# plugV15.net
KiCad netlist of a schematic drawn in EAGLE
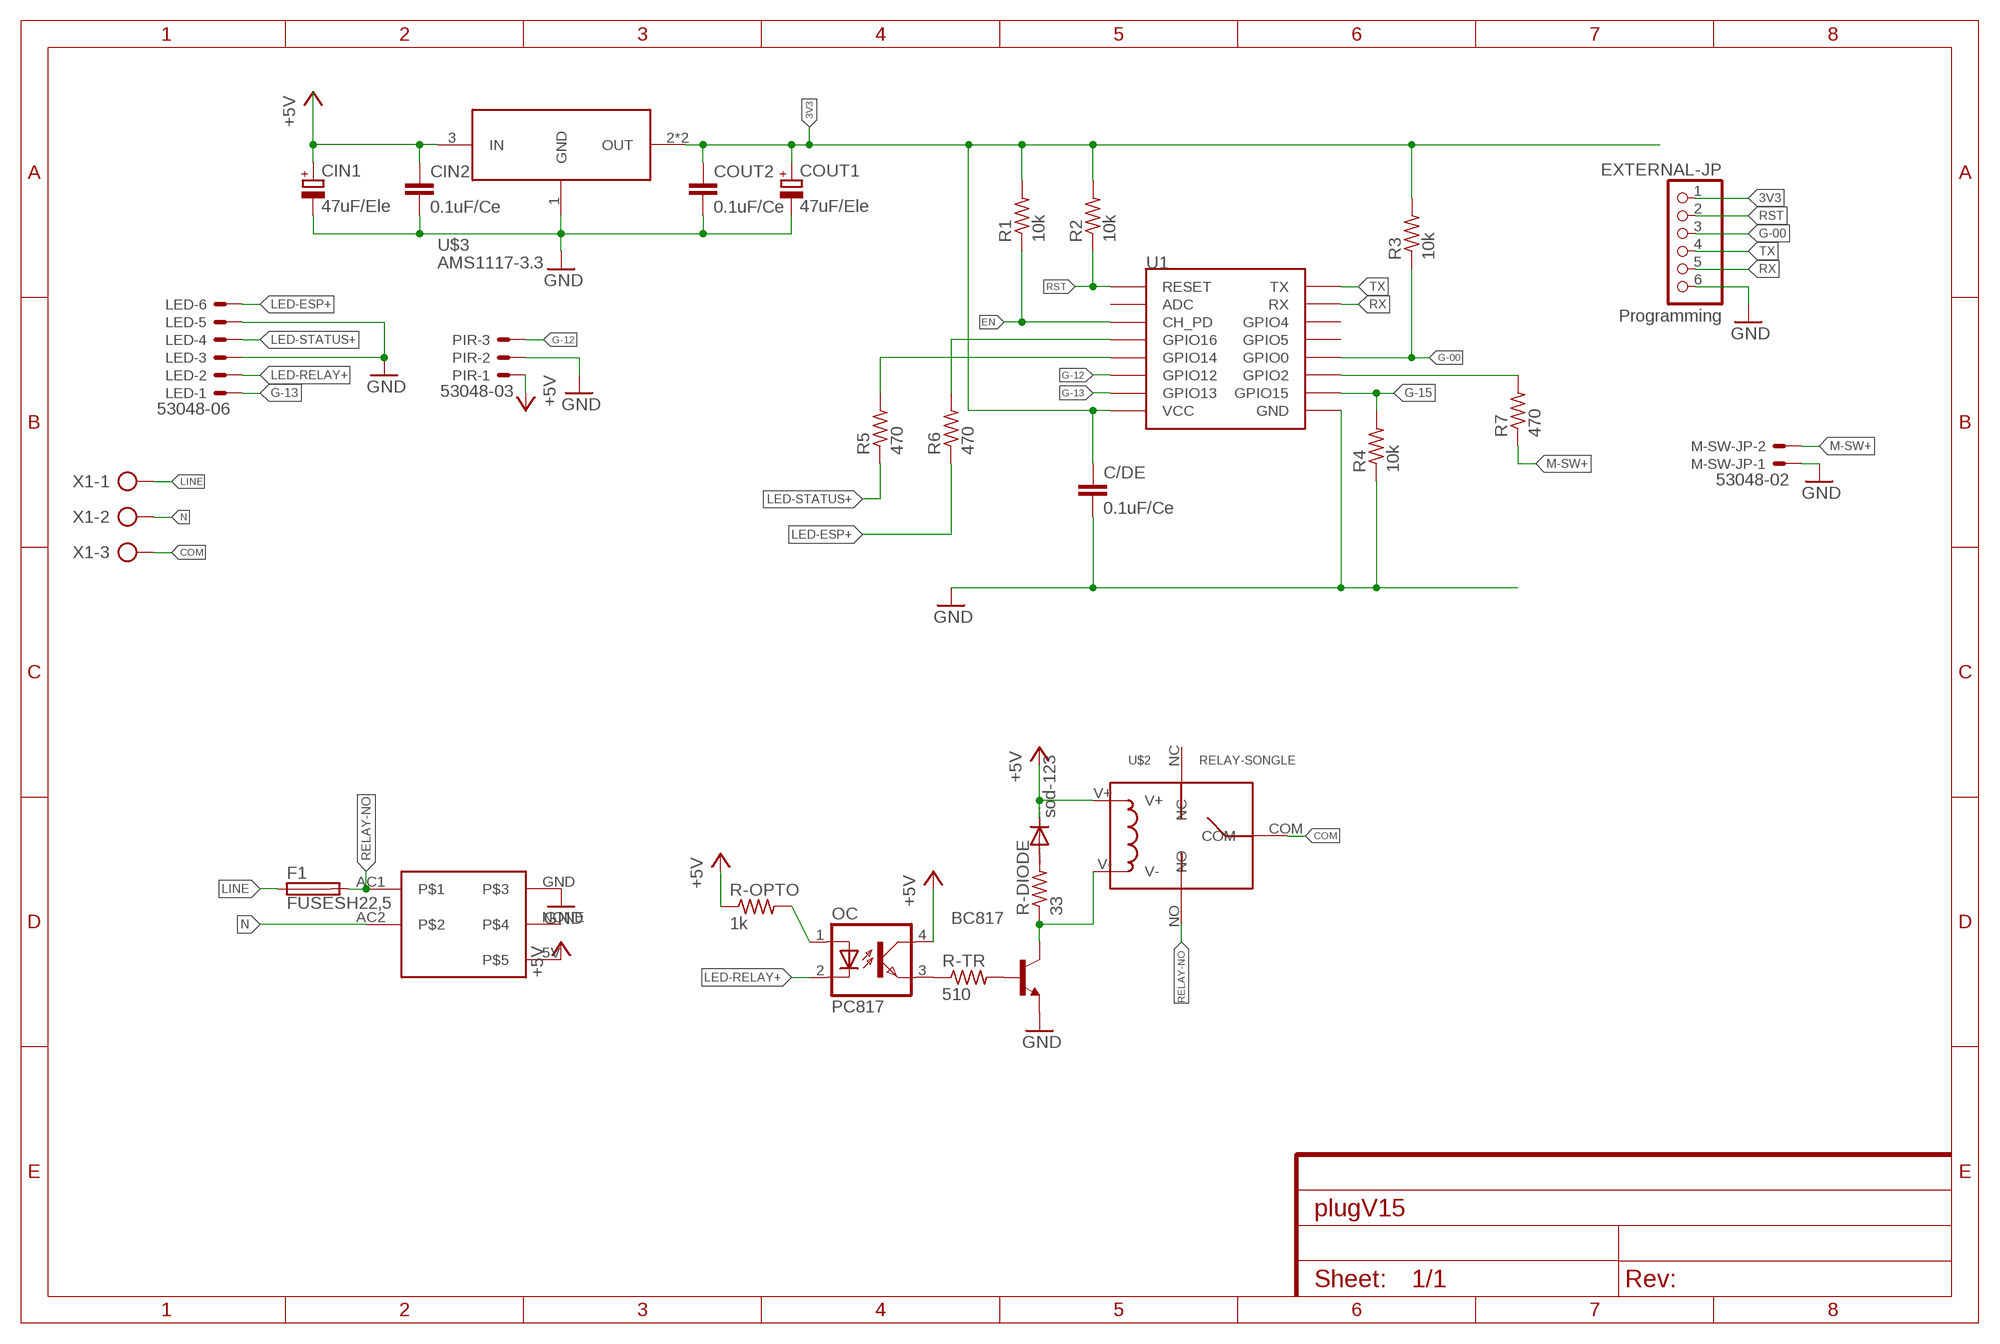
[diagram p0: schematic, sheet 1]

(export (version "E")
  (design (tool "Eeschema 10.0.6"))
  (components
    (comp (ref "1N4148")
      (value "sod-123")
      (footprint "eagle-import:SOD-123_MINI-SMA")
      (libsource (lib "eagle-import") (part "CGRM400-G1"))
    )
    (comp (ref "BC817")
      (value "BC817-NPN-SOT23-BEC")
      (footprint "eagle-import:SOT23-BEC")
      (libsource (lib "eagle-import") (part "-NPN-SOT23-BECBC817"))
    )
    (comp (ref "C/DE")
      (value "0.1uF/Ce")
      (footprint "eagle-import:C0805")
      (libsource (lib "eagle-import") (part "C-EUC0805"))
    )
    (comp (ref "CIN1")
      (value "47uF/Ele")
      (footprint "eagle-import:E2-5")
      (libsource (lib "eagle-import") (part "CPOL-EUE2-5"))
    )
    (comp (ref "CIN2")
      (value "0.1uF/Ce")
      (footprint "eagle-import:C0805")
      (libsource (lib "eagle-import") (part "C-EUC0805"))
    )
    (comp (ref "COUT1")
      (value "47uF/Ele")
      (footprint "eagle-import:E2-5")
      (libsource (lib "eagle-import") (part "CPOL-EUE2-5"))
    )
    (comp (ref "COUT2")
      (value "0.1uF/Ce")
      (footprint "eagle-import:C0805")
      (libsource (lib "eagle-import") (part "C-EUC0805"))
    )
    (comp (ref "EXTERNAL-JP")
      (value "Programming")
      (footprint "eagle-import:1X06")
      (libsource (lib "eagle-import") (part "PINHD-1X6"))
    )
    (comp (ref "F1")
      (value "FUSESH22,5")
      (footprint "eagle-import:SH22,5")
      (libsource (lib "eagle-import") (part "FUSESH22,5"))
    )
    (comp (ref "LED")
      (value "53048-06")
      (footprint "eagle-import:53048-06")
      (fields (field (name "MF") "WALDOM/MOLEX") (field (name "MPN") "53048-0610"))
      (libsource (lib "eagle-import") (part "53?-06048"))
    )
    (comp (ref "M-SW-JP")
      (value "53048-02")
      (footprint "eagle-import:53048-02")
      (fields (field (name "MF") "MOLEX") (field (name "MPN") "53048-0210"))
      (libsource (lib "eagle-import") (part "53?-02048"))
    )
    (comp (ref "OC")
      (value "PC817")
      (footprint "eagle-import:DIL04")
      (fields (field (name "MPN") "PC817X4J000F"))
      (libsource (lib "eagle-import") (part "PC817"))
    )
    (comp (ref "PIR")
      (value "53048-03")
      (footprint "eagle-import:53048-03")
      (fields (field (name "MF") "WALDOM/MOLEX") (field (name "MPN") "53048-0310"))
      (libsource (lib "eagle-import") (part "53?-03048"))
    )
    (comp (ref "R-DIODE")
      (value "33")
      (footprint "eagle-import:R0805")
      (libsource (lib "eagle-import") (part "R-US_R0805"))
    )
    (comp (ref "R-OPTO")
      (value "1k")
      (footprint "eagle-import:R0805")
      (libsource (lib "eagle-import") (part "R-US_R0805"))
    )
    (comp (ref "R-TR")
      (value "510")
      (footprint "eagle-import:R0805")
      (libsource (lib "eagle-import") (part "R-US_R0805"))
    )
    (comp (ref "R1")
      (value "10k")
      (footprint "eagle-import:0207_10")
      (libsource (lib "eagle-import") (part "R-US_0207/10"))
    )
    (comp (ref "R2")
      (value "10k")
      (footprint "eagle-import:0207_10")
      (libsource (lib "eagle-import") (part "R-US_0207/10"))
    )
    (comp (ref "R3")
      (value "10k")
      (footprint "eagle-import:0207_10")
      (libsource (lib "eagle-import") (part "R-US_0207/10"))
    )
    (comp (ref "R4")
      (value "10k")
      (footprint "eagle-import:0207_10")
      (libsource (lib "eagle-import") (part "R-US_0207/10"))
    )
    (comp (ref "R5")
      (value "470")
      (footprint "eagle-import:0207_10")
      (libsource (lib "eagle-import") (part "R-US_0207/10"))
    )
    (comp (ref "R6")
      (value "470")
      (footprint "eagle-import:0207_10")
      (libsource (lib "eagle-import") (part "R-US_0207/10"))
    )
    (comp (ref "R7")
      (value "470")
      (footprint "eagle-import:0207_10")
      (libsource (lib "eagle-import") (part "R-US_0207/10"))
    )
    (comp (ref "U$2")
      (value "RELAY-SONGLE")
      (footprint "eagle-import:RELAY-SONGLE")
      (libsource (lib "eagle-import") (part "RELAY-SONGLE"))
    )
    (comp (ref "U$3")
      (value "AMS1117-3.3")
      (footprint "eagle-import:SOT-223")
      (libsource (lib "eagle-import") (part "AMS1117-3.3"))
    )
    (comp (ref "U$4")
      (value "POWERSUPPLY-5V-700MA")
      (footprint "eagle-import:POWERSUPPLY-5V-700MA")
      (libsource (lib "eagle-import") (part "POWERSUPPLY-5V-700MA"))
    )
    (comp (ref "U1")
      (value "ESP12SMD")
      (footprint "eagle-import:ESP12-SMD")
      (libsource (lib "eagle-import") (part "ESP12SMD"))
    )
    (comp (ref "X1")
      (value "AK300/3")
      (footprint "eagle-import:AK300_3")
      (libsource (lib "eagle-import") (part "AK300/3"))
    )
  )
  (nets
    (net (code "1") (name "+5V") (class "Default")
      (node (ref "1N4148") (pin "C") (pinfunction "C_C") (pintype "passive"))
      (node (ref "CIN1") (pin "+") (pinfunction "+_+") (pintype "passive"))
      (node (ref "CIN2") (pin "1") (pinfunction "1_1") (pintype "passive"))
      (node (ref "OC") (pin "4") (pinfunction "COL_4") (pintype "passive"))
      (node (ref "PIR") (pin "1") (pinfunction "S_1") (pintype "passive"))
      (node (ref "R-OPTO") (pin "1") (pinfunction "1_1") (pintype "passive"))
      (node (ref "U$2") (pin "V+") (pinfunction "V+_V+") (pintype "bidirectional"))
      (node (ref "U$3") (pin "3") (pinfunction "IN_3") (pintype "input"))
      (node (ref "U$4") (pin "5V") (pinfunction "P$5_5V") (pintype "bidirectional"))
    )
    (net (code "2") (name "3V3") (class "Default")
      (node (ref "C/DE") (pin "1") (pinfunction "1_1") (pintype "passive"))
      (node (ref "COUT1") (pin "+") (pinfunction "+_+") (pintype "passive"))
      (node (ref "COUT2") (pin "1") (pinfunction "1_1") (pintype "passive"))
      (node (ref "EXTERNAL-JP") (pin "1") (pinfunction "1_1") (pintype "passive"))
      (node (ref "R1") (pin "2") (pinfunction "2_2") (pintype "passive"))
      (node (ref "R2") (pin "2") (pinfunction "2_2") (pintype "passive"))
      (node (ref "R3") (pin "2") (pinfunction "2_2") (pintype "passive"))
      (node (ref "U$3") (pin "2") (pinfunction "OUT_2") (pintype "output"))
      (node (ref "U$3") (pin "4") (pinfunction "OUT_4") (pintype "output"))
      (node (ref "U1") (pin "VCC") (pinfunction "VCC_VCC") (pintype "bidirectional"))
    )
    (net (code "3") (name "COM") (class "Default")
      (node (ref "U$2") (pin "COM") (pinfunction "COM_COM") (pintype "bidirectional"))
      (node (ref "X1") (pin "3") (pinfunction "KL_3") (pintype "passive"))
    )
    (net (code "4") (name "EN") (class "Default")
      (node (ref "R1") (pin "1") (pinfunction "1_1") (pintype "passive"))
      (node (ref "U1") (pin "CH_PD") (pinfunction "CH_PD_CH_PD") (pintype "bidirectional"))
    )
    (net (code "5") (name "G-00") (class "Default")
      (node (ref "EXTERNAL-JP") (pin "3") (pinfunction "3_3") (pintype "passive"))
      (node (ref "R3") (pin "1") (pinfunction "1_1") (pintype "passive"))
      (node (ref "U1") (pin "GPIO0") (pinfunction "GPIO0_GPIO0") (pintype "bidirectional"))
    )
    (net (code "6") (name "G-12") (class "Default")
      (node (ref "PIR") (pin "3") (pinfunction "S_3") (pintype "passive"))
      (node (ref "U1") (pin "GPIO12") (pinfunction "GPIO12_GPIO12") (pintype "bidirectional"))
    )
    (net (code "7") (name "G-13") (class "Default")
      (node (ref "LED") (pin "1") (pinfunction "S_1") (pintype "passive"))
      (node (ref "U1") (pin "GPIO13") (pinfunction "GPIO13_GPIO13") (pintype "bidirectional"))
    )
    (net (code "8") (name "G-15") (class "Default")
      (node (ref "R4") (pin "2") (pinfunction "2_2") (pintype "passive"))
      (node (ref "U1") (pin "GPIO15") (pinfunction "GPIO15_GPIO15") (pintype "bidirectional"))
    )
    (net (code "9") (name "GND") (class "Default")
      (node (ref "BC817") (pin "E") (pinfunction "E_E") (pintype "passive"))
      (node (ref "C/DE") (pin "2") (pinfunction "2_2") (pintype "passive"))
      (node (ref "CIN1") (pin "-") (pinfunction "-_-") (pintype "passive"))
      (node (ref "CIN2") (pin "2") (pinfunction "2_2") (pintype "passive"))
      (node (ref "COUT1") (pin "-") (pinfunction "-_-") (pintype "passive"))
      (node (ref "COUT2") (pin "2") (pinfunction "2_2") (pintype "passive"))
      (node (ref "EXTERNAL-JP") (pin "6") (pinfunction "6_6") (pintype "passive"))
      (node (ref "LED") (pin "3") (pinfunction "S_3") (pintype "passive"))
      (node (ref "LED") (pin "5") (pinfunction "S_5") (pintype "passive"))
      (node (ref "M-SW-JP") (pin "1") (pinfunction "S_1") (pintype "passive"))
      (node (ref "PIR") (pin "2") (pinfunction "S_2") (pintype "passive"))
      (node (ref "R4") (pin "1") (pinfunction "1_1") (pintype "passive"))
      (node (ref "U$3") (pin "1") (pinfunction "GND_1") (pintype "passive"))
      (node (ref "U$4") (pin "GND") (pinfunction "P$3_GND") (pintype "bidirectional"))
      (node (ref "U1") (pin "GND") (pinfunction "GND_GND") (pintype "bidirectional"))
    )
    (net (code "10") (name "LED-ESP+") (class "Default")
      (node (ref "LED") (pin "6") (pinfunction "S_6") (pintype "passive"))
      (node (ref "R6") (pin "1") (pinfunction "1_1") (pintype "passive"))
    )
    (net (code "11") (name "LED-RELAY+") (class "Default")
      (node (ref "LED") (pin "2") (pinfunction "S_2") (pintype "passive"))
      (node (ref "OC") (pin "2") (pinfunction "C_2") (pintype "passive"))
    )
    (net (code "12") (name "LED-STATUS+") (class "Default")
      (node (ref "LED") (pin "4") (pinfunction "S_4") (pintype "passive"))
      (node (ref "R5") (pin "1") (pinfunction "1_1") (pintype "passive"))
    )
    (net (code "13") (name "LINE") (class "Default")
      (node (ref "F1") (pin "1") (pinfunction "1_1") (pintype "passive"))
      (node (ref "X1") (pin "1") (pinfunction "KL_1") (pintype "passive"))
    )
    (net (code "14") (name "M-SW+") (class "Default")
      (node (ref "M-SW-JP") (pin "2") (pinfunction "S_2") (pintype "passive"))
      (node (ref "R7") (pin "1") (pinfunction "1_1") (pintype "passive"))
    )
    (net (code "15") (name "N") (class "Default")
      (node (ref "U$4") (pin "AC2") (pinfunction "P$2_AC2") (pintype "bidirectional"))
      (node (ref "X1") (pin "2") (pinfunction "KL_2") (pintype "passive"))
    )
    (net (code "16") (name "Net-(1N4148-PadA)") (class "Default")
      (node (ref "1N4148") (pin "A") (pinfunction "A_A") (pintype "passive"))
      (node (ref "R-DIODE") (pin "2") (pinfunction "2_2") (pintype "passive"))
    )
    (net (code "17") (name "Net-(BC817-PadB)") (class "Default")
      (node (ref "BC817") (pin "B") (pinfunction "B_B") (pintype "passive"))
      (node (ref "R-TR") (pin "2") (pinfunction "2_2") (pintype "passive"))
    )
    (net (code "18") (name "Net-(BC817-PadC)") (class "Default")
      (node (ref "BC817") (pin "C") (pinfunction "C_C") (pintype "passive"))
      (node (ref "R-DIODE") (pin "1") (pinfunction "1_1") (pintype "passive"))
      (node (ref "U$2") (pin "V-") (pinfunction "V-_V-") (pintype "bidirectional"))
    )
    (net (code "19") (name "Net-(OC-A)") (class "Default")
      (node (ref "OC") (pin "1") (pinfunction "A_1") (pintype "passive"))
      (node (ref "R-OPTO") (pin "2") (pinfunction "2_2") (pintype "passive"))
    )
    (net (code "20") (name "Net-(OC-EMIT)") (class "Default")
      (node (ref "OC") (pin "3") (pinfunction "EMIT_3") (pintype "passive"))
      (node (ref "R-TR") (pin "1") (pinfunction "1_1") (pintype "passive"))
    )
    (net (code "21") (name "Net-(R5-Pad2)") (class "Default")
      (node (ref "R5") (pin "2") (pinfunction "2_2") (pintype "passive"))
      (node (ref "U1") (pin "GPIO14") (pinfunction "GPIO14_GPIO14") (pintype "bidirectional"))
    )
    (net (code "22") (name "Net-(R6-Pad2)") (class "Default")
      (node (ref "R6") (pin "2") (pinfunction "2_2") (pintype "passive"))
      (node (ref "U1") (pin "GPIO16") (pinfunction "GPIO16_GPIO16") (pintype "bidirectional"))
    )
    (net (code "23") (name "Net-(R7-Pad2)") (class "Default")
      (node (ref "R7") (pin "2") (pinfunction "2_2") (pintype "passive"))
      (node (ref "U1") (pin "GPIO2") (pinfunction "GPIO2_GPIO2") (pintype "bidirectional"))
    )
    (net (code "24") (name "RELAY-NO") (class "Default")
      (node (ref "F1") (pin "2") (pinfunction "2_2") (pintype "passive"))
      (node (ref "U$2") (pin "NO") (pinfunction "NO_NO") (pintype "bidirectional"))
      (node (ref "U$4") (pin "AC1") (pinfunction "P$1_AC1") (pintype "bidirectional"))
    )
    (net (code "25") (name "RST") (class "Default")
      (node (ref "EXTERNAL-JP") (pin "2") (pinfunction "2_2") (pintype "passive"))
      (node (ref "R2") (pin "1") (pinfunction "1_1") (pintype "passive"))
      (node (ref "U1") (pin "RESET") (pinfunction "RESET_RESET") (pintype "bidirectional"))
    )
    (net (code "26") (name "RX") (class "Default")
      (node (ref "EXTERNAL-JP") (pin "5") (pinfunction "5_5") (pintype "passive"))
      (node (ref "U1") (pin "RXD0") (pinfunction "RX_RXD0") (pintype "bidirectional"))
    )
    (net (code "27") (name "TX") (class "Default")
      (node (ref "EXTERNAL-JP") (pin "4") (pinfunction "4_4") (pintype "passive"))
      (node (ref "U1") (pin "TXD0") (pinfunction "TX_TXD0") (pintype "bidirectional"))
    )
    (net (code "28") (name "unconnected-(U$2-PadNC)") (class "Default")
      (node (ref "U$2") (pin "NC") (pinfunction "NC_NC") (pintype "bidirectional"))
    )
    (net (code "29") (name "unconnected-(U$4-P$4-PadNONE)") (class "Default")
      (node (ref "U$4") (pin "NONE") (pinfunction "P$4_NONE") (pintype "bidirectional"))
    )
    (net (code "30") (name "unconnected-(U1-PadADC)") (class "Default")
      (node (ref "U1") (pin "ADC") (pinfunction "ADC_ADC") (pintype "bidirectional"))
    )
    (net (code "31") (name "unconnected-(U1-PadGPIO4)") (class "Default")
      (node (ref "U1") (pin "GPIO4") (pinfunction "GPIO4_GPIO4") (pintype "bidirectional"))
    )
    (net (code "32") (name "unconnected-(U1-PadGPIO5)") (class "Default")
      (node (ref "U1") (pin "GPIO5") (pinfunction "GPIO5_GPIO5") (pintype "bidirectional"))
    )
  )
)
